# MB1075.net
KiCad netlist of a schematic drawn in Altium Designer
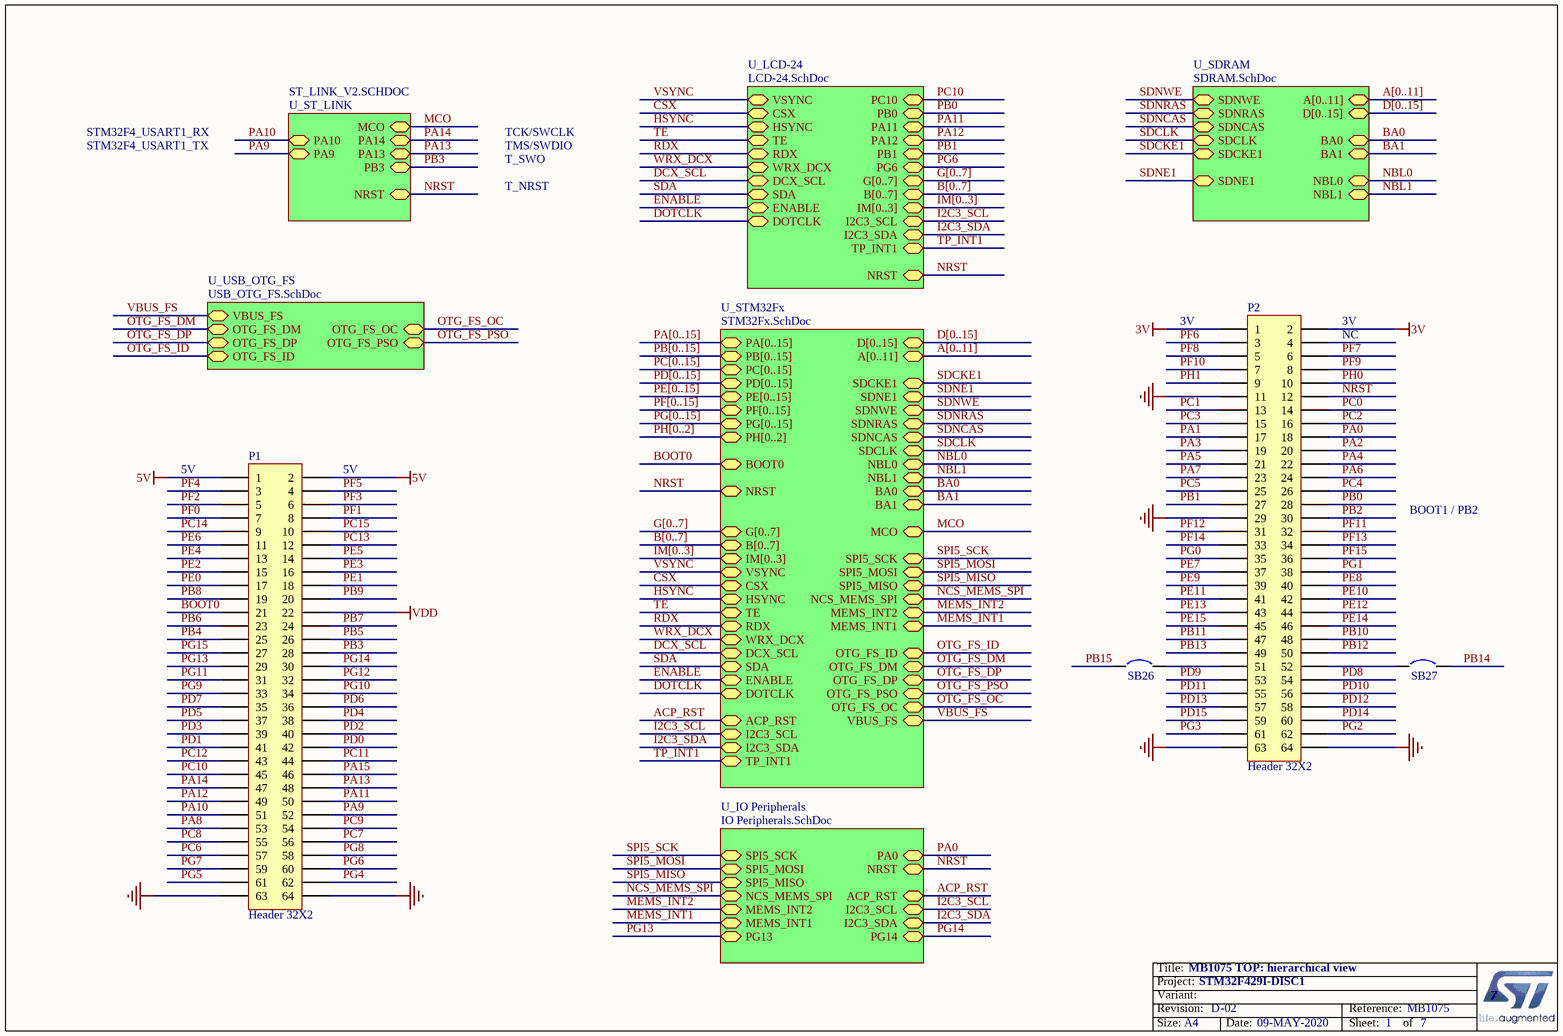
[diagram p0: MB1075.SchDoc]

(export (version "E")
  (design (tool "Eeschema 10.0.6"))
  (components
    (comp (ref "P1")
      (value "Header 32X2")
      (footprint "HDR2X32")
      (description "Header, 32-Pin, Dual row")
      (fields (field (name "PUBLISHER") "Altium Limited"))
      (libsource (lib "MCD_TOOLS") (part "Header 32X2"))
    )
    (comp (ref "P2")
      (value "Header 32X2")
      (footprint "HDR2X32")
      (description "Header, 32-Pin, Dual row")
      (fields (field (name "PUBLISHER") "Altium Limited"))
      (libsource (lib "MCD_TOOLS") (part "Header 32X2"))
    )
    (comp (ref "SB26")
      (value "Circuit Breaker")
      (footprint "JP2_SMD")
      (fields (field (name "PUBLISHER") "Altium Limited"))
      (libsource (lib "MCD_TOOLS") (part "Circuit Breaker"))
    )
    (comp (ref "SB27")
      (value "Circuit Breaker")
      (footprint "JP2_SMD")
      (fields (field (name "PUBLISHER") "Altium Limited"))
      (libsource (lib "MCD_TOOLS") (part "Circuit Breaker"))
    )
  )
  (nets
    (net (code "54") (name "/BOOT0") (class "Default")
      (node (ref "P1") (pin "21") (pinfunction "21_21") (pintype "passive"))
    )
    (net (code "72") (name "/NRST") (class "Default")
      (node (ref "P2") (pin "12") (pinfunction "12_12") (pintype "passive"))
    )
    (net (code "78") (name "/PA0") (class "Default")
      (node (ref "P2") (pin "18") (pinfunction "18_18") (pintype "passive"))
    )
    (net (code "79") (name "/PA1") (class "Default")
      (node (ref "P2") (pin "17") (pinfunction "17_17") (pintype "passive"))
    )
    (net (code "80") (name "/PA2") (class "Default")
      (node (ref "P2") (pin "20") (pinfunction "20_20") (pintype "passive"))
    )
    (net (code "81") (name "/PA3") (class "Default")
      (node (ref "P2") (pin "19") (pinfunction "19_19") (pintype "passive"))
    )
    (net (code "82") (name "/PA4") (class "Default")
      (node (ref "P2") (pin "22") (pinfunction "22_22") (pintype "passive"))
    )
    (net (code "83") (name "/PA5") (class "Default")
      (node (ref "P2") (pin "21") (pinfunction "21_21") (pintype "passive"))
    )
    (net (code "84") (name "/PA6") (class "Default")
      (node (ref "P2") (pin "24") (pinfunction "24_24") (pintype "passive"))
    )
    (net (code "85") (name "/PA7") (class "Default")
      (node (ref "P2") (pin "23") (pinfunction "23_23") (pintype "passive"))
    )
    (net (code "86") (name "/PA8") (class "Default")
      (node (ref "P1") (pin "53") (pinfunction "53_53") (pintype "passive"))
    )
    (net (code "87") (name "/PA9") (class "Default")
      (node (ref "P1") (pin "52") (pinfunction "52_52") (pintype "passive"))
    )
    (net (code "88") (name "/PA10") (class "Default")
      (node (ref "P1") (pin "51") (pinfunction "51_51") (pintype "passive"))
    )
    (net (code "89") (name "/PA11") (class "Default")
      (node (ref "P1") (pin "50") (pinfunction "50_50") (pintype "passive"))
    )
    (net (code "90") (name "/PA12") (class "Default")
      (node (ref "P1") (pin "49") (pinfunction "49_49") (pintype "passive"))
    )
    (net (code "91") (name "/PA13") (class "Default")
      (node (ref "P1") (pin "48") (pinfunction "48_48") (pintype "passive"))
    )
    (net (code "92") (name "/PA14") (class "Default")
      (node (ref "P1") (pin "47") (pinfunction "47_47") (pintype "passive"))
    )
    (net (code "93") (name "/PA15") (class "Default")
      (node (ref "P1") (pin "46") (pinfunction "46_46") (pintype "passive"))
    )
    (net (code "95") (name "/PB0") (class "Default")
      (node (ref "P2") (pin "28") (pinfunction "28_28") (pintype "passive"))
    )
    (net (code "96") (name "/PB1") (class "Default")
      (node (ref "P2") (pin "27") (pinfunction "27_27") (pintype "passive"))
    )
    (net (code "97") (name "/PB2") (class "Default")
      (node (ref "P2") (pin "30") (pinfunction "30_30") (pintype "passive"))
    )
    (net (code "98") (name "/PB3") (class "Default")
      (node (ref "P1") (pin "28") (pinfunction "28_28") (pintype "passive"))
    )
    (net (code "99") (name "/PB4") (class "Default")
      (node (ref "P1") (pin "25") (pinfunction "25_25") (pintype "passive"))
    )
    (net (code "100") (name "/PB5") (class "Default")
      (node (ref "P1") (pin "26") (pinfunction "26_26") (pintype "passive"))
    )
    (net (code "101") (name "/PB6") (class "Default")
      (node (ref "P1") (pin "23") (pinfunction "23_23") (pintype "passive"))
    )
    (net (code "102") (name "/PB7") (class "Default")
      (node (ref "P1") (pin "24") (pinfunction "24_24") (pintype "passive"))
    )
    (net (code "103") (name "/PB8") (class "Default")
      (node (ref "P1") (pin "19") (pinfunction "19_19") (pintype "passive"))
    )
    (net (code "104") (name "/PB9") (class "Default")
      (node (ref "P1") (pin "20") (pinfunction "20_20") (pintype "passive"))
    )
    (net (code "105") (name "/PB10") (class "Default")
      (node (ref "P2") (pin "48") (pinfunction "48_48") (pintype "passive"))
    )
    (net (code "106") (name "/PB11") (class "Default")
      (node (ref "P2") (pin "47") (pinfunction "47_47") (pintype "passive"))
    )
    (net (code "107") (name "/PB12") (class "Default")
      (node (ref "P2") (pin "50") (pinfunction "50_50") (pintype "passive"))
    )
    (net (code "108") (name "/PB13") (class "Default")
      (node (ref "P2") (pin "49") (pinfunction "49_49") (pintype "passive"))
    )
    (net (code "109") (name "/PB14") (class "Default")
      (node (ref "SB27") (pin "2") (pinfunction "2_2") (pintype "passive"))
    )
    (net (code "110") (name "/PB15") (class "Default")
      (node (ref "SB26") (pin "1") (pinfunction "1_1") (pintype "passive"))
    )
    (net (code "112") (name "/PC0") (class "Default")
      (node (ref "P2") (pin "14") (pinfunction "14_14") (pintype "passive"))
    )
    (net (code "113") (name "/PC1") (class "Default")
      (node (ref "P2") (pin "13") (pinfunction "13_13") (pintype "passive"))
    )
    (net (code "114") (name "/PC2") (class "Default")
      (node (ref "P2") (pin "16") (pinfunction "16_16") (pintype "passive"))
    )
    (net (code "115") (name "/PC3") (class "Default")
      (node (ref "P2") (pin "15") (pinfunction "15_15") (pintype "passive"))
    )
    (net (code "116") (name "/PC4") (class "Default")
      (node (ref "P2") (pin "26") (pinfunction "26_26") (pintype "passive"))
    )
    (net (code "117") (name "/PC5") (class "Default")
      (node (ref "P2") (pin "25") (pinfunction "25_25") (pintype "passive"))
    )
    (net (code "118") (name "/PC6") (class "Default")
      (node (ref "P1") (pin "57") (pinfunction "57_57") (pintype "passive"))
    )
    (net (code "119") (name "/PC7") (class "Default")
      (node (ref "P1") (pin "56") (pinfunction "56_56") (pintype "passive"))
    )
    (net (code "120") (name "/PC8") (class "Default")
      (node (ref "P1") (pin "55") (pinfunction "55_55") (pintype "passive"))
    )
    (net (code "121") (name "/PC9") (class "Default")
      (node (ref "P1") (pin "54") (pinfunction "54_54") (pintype "passive"))
    )
    (net (code "122") (name "/PC10") (class "Default")
      (node (ref "P1") (pin "45") (pinfunction "45_45") (pintype "passive"))
    )
    (net (code "123") (name "/PC11") (class "Default")
      (node (ref "P1") (pin "44") (pinfunction "44_44") (pintype "passive"))
    )
    (net (code "124") (name "/PC12") (class "Default")
      (node (ref "P1") (pin "43") (pinfunction "43_43") (pintype "passive"))
    )
    (net (code "125") (name "/PC13") (class "Default")
      (node (ref "P1") (pin "12") (pinfunction "12_12") (pintype "passive"))
    )
    (net (code "126") (name "/PC14") (class "Default")
      (node (ref "P1") (pin "9") (pinfunction "9_9") (pintype "passive"))
    )
    (net (code "127") (name "/PC15") (class "Default")
      (node (ref "P1") (pin "10") (pinfunction "10_10") (pintype "passive"))
    )
    (net (code "129") (name "/PD0") (class "Default")
      (node (ref "P1") (pin "42") (pinfunction "42_42") (pintype "passive"))
    )
    (net (code "130") (name "/PD1") (class "Default")
      (node (ref "P1") (pin "41") (pinfunction "41_41") (pintype "passive"))
    )
    (net (code "131") (name "/PD2") (class "Default")
      (node (ref "P1") (pin "40") (pinfunction "40_40") (pintype "passive"))
    )
    (net (code "132") (name "/PD3") (class "Default")
      (node (ref "P1") (pin "39") (pinfunction "39_39") (pintype "passive"))
    )
    (net (code "133") (name "/PD4") (class "Default")
      (node (ref "P1") (pin "38") (pinfunction "38_38") (pintype "passive"))
    )
    (net (code "134") (name "/PD5") (class "Default")
      (node (ref "P1") (pin "37") (pinfunction "37_37") (pintype "passive"))
    )
    (net (code "135") (name "/PD6") (class "Default")
      (node (ref "P1") (pin "36") (pinfunction "36_36") (pintype "passive"))
    )
    (net (code "136") (name "/PD7") (class "Default")
      (node (ref "P1") (pin "35") (pinfunction "35_35") (pintype "passive"))
    )
    (net (code "137") (name "/PD8") (class "Default")
      (node (ref "P2") (pin "54") (pinfunction "54_54") (pintype "passive"))
    )
    (net (code "138") (name "/PD9") (class "Default")
      (node (ref "P2") (pin "53") (pinfunction "53_53") (pintype "passive"))
    )
    (net (code "139") (name "/PD10") (class "Default")
      (node (ref "P2") (pin "56") (pinfunction "56_56") (pintype "passive"))
    )
    (net (code "140") (name "/PD11") (class "Default")
      (node (ref "P2") (pin "55") (pinfunction "55_55") (pintype "passive"))
    )
    (net (code "141") (name "/PD12") (class "Default")
      (node (ref "P2") (pin "58") (pinfunction "58_58") (pintype "passive"))
    )
    (net (code "142") (name "/PD13") (class "Default")
      (node (ref "P2") (pin "57") (pinfunction "57_57") (pintype "passive"))
    )
    (net (code "143") (name "/PD14") (class "Default")
      (node (ref "P2") (pin "60") (pinfunction "60_60") (pintype "passive"))
    )
    (net (code "144") (name "/PD15") (class "Default")
      (node (ref "P2") (pin "59") (pinfunction "59_59") (pintype "passive"))
    )
    (net (code "146") (name "/PE0") (class "Default")
      (node (ref "P1") (pin "17") (pinfunction "17_17") (pintype "passive"))
    )
    (net (code "147") (name "/PE1") (class "Default")
      (node (ref "P1") (pin "18") (pinfunction "18_18") (pintype "passive"))
    )
    (net (code "148") (name "/PE2") (class "Default")
      (node (ref "P1") (pin "15") (pinfunction "15_15") (pintype "passive"))
    )
    (net (code "149") (name "/PE3") (class "Default")
      (node (ref "P1") (pin "16") (pinfunction "16_16") (pintype "passive"))
    )
    (net (code "150") (name "/PE4") (class "Default")
      (node (ref "P1") (pin "13") (pinfunction "13_13") (pintype "passive"))
    )
    (net (code "151") (name "/PE5") (class "Default")
      (node (ref "P1") (pin "14") (pinfunction "14_14") (pintype "passive"))
    )
    (net (code "152") (name "/PE6") (class "Default")
      (node (ref "P1") (pin "11") (pinfunction "11_11") (pintype "passive"))
    )
    (net (code "153") (name "/PE7") (class "Default")
      (node (ref "P2") (pin "37") (pinfunction "37_37") (pintype "passive"))
    )
    (net (code "154") (name "/PE8") (class "Default")
      (node (ref "P2") (pin "40") (pinfunction "40_40") (pintype "passive"))
    )
    (net (code "155") (name "/PE9") (class "Default")
      (node (ref "P2") (pin "39") (pinfunction "39_39") (pintype "passive"))
    )
    (net (code "156") (name "/PE10") (class "Default")
      (node (ref "P2") (pin "42") (pinfunction "42_42") (pintype "passive"))
    )
    (net (code "157") (name "/PE11") (class "Default")
      (node (ref "P2") (pin "41") (pinfunction "41_41") (pintype "passive"))
    )
    (net (code "158") (name "/PE12") (class "Default")
      (node (ref "P2") (pin "44") (pinfunction "44_44") (pintype "passive"))
    )
    (net (code "159") (name "/PE13") (class "Default")
      (node (ref "P2") (pin "43") (pinfunction "43_43") (pintype "passive"))
    )
    (net (code "160") (name "/PE14") (class "Default")
      (node (ref "P2") (pin "46") (pinfunction "46_46") (pintype "passive"))
    )
    (net (code "161") (name "/PE15") (class "Default")
      (node (ref "P2") (pin "45") (pinfunction "45_45") (pintype "passive"))
    )
    (net (code "163") (name "/PF0") (class "Default")
      (node (ref "P1") (pin "7") (pinfunction "7_7") (pintype "passive"))
    )
    (net (code "164") (name "/PF1") (class "Default")
      (node (ref "P1") (pin "8") (pinfunction "8_8") (pintype "passive"))
    )
    (net (code "165") (name "/PF2") (class "Default")
      (node (ref "P1") (pin "5") (pinfunction "5_5") (pintype "passive"))
    )
    (net (code "166") (name "/PF3") (class "Default")
      (node (ref "P1") (pin "6") (pinfunction "6_6") (pintype "passive"))
    )
    (net (code "167") (name "/PF4") (class "Default")
      (node (ref "P1") (pin "3") (pinfunction "3_3") (pintype "passive"))
    )
    (net (code "168") (name "/PF5") (class "Default")
      (node (ref "P1") (pin "4") (pinfunction "4_4") (pintype "passive"))
    )
    (net (code "169") (name "/PF6") (class "Default")
      (node (ref "P2") (pin "3") (pinfunction "3_3") (pintype "passive"))
    )
    (net (code "170") (name "/PF7") (class "Default")
      (node (ref "P2") (pin "6") (pinfunction "6_6") (pintype "passive"))
    )
    (net (code "171") (name "/PF8") (class "Default")
      (node (ref "P2") (pin "5") (pinfunction "5_5") (pintype "passive"))
    )
    (net (code "172") (name "/PF9") (class "Default")
      (node (ref "P2") (pin "8") (pinfunction "8_8") (pintype "passive"))
    )
    (net (code "173") (name "/PF10") (class "Default")
      (node (ref "P2") (pin "7") (pinfunction "7_7") (pintype "passive"))
    )
    (net (code "174") (name "/PF11") (class "Default")
      (node (ref "P2") (pin "32") (pinfunction "32_32") (pintype "passive"))
    )
    (net (code "175") (name "/PF12") (class "Default")
      (node (ref "P2") (pin "31") (pinfunction "31_31") (pintype "passive"))
    )
    (net (code "176") (name "/PF13") (class "Default")
      (node (ref "P2") (pin "34") (pinfunction "34_34") (pintype "passive"))
    )
    (net (code "177") (name "/PF14") (class "Default")
      (node (ref "P2") (pin "33") (pinfunction "33_33") (pintype "passive"))
    )
    (net (code "178") (name "/PF15") (class "Default")
      (node (ref "P2") (pin "36") (pinfunction "36_36") (pintype "passive"))
    )
    (net (code "180") (name "/PG0") (class "Default")
      (node (ref "P2") (pin "35") (pinfunction "35_35") (pintype "passive"))
    )
    (net (code "181") (name "/PG1") (class "Default")
      (node (ref "P2") (pin "38") (pinfunction "38_38") (pintype "passive"))
    )
    (net (code "182") (name "/PG2") (class "Default")
      (node (ref "P2") (pin "62") (pinfunction "62_62") (pintype "passive"))
    )
    (net (code "183") (name "/PG3") (class "Default")
      (node (ref "P2") (pin "61") (pinfunction "61_61") (pintype "passive"))
    )
    (net (code "184") (name "/PG4") (class "Default")
      (node (ref "P1") (pin "62") (pinfunction "62_62") (pintype "passive"))
    )
    (net (code "185") (name "/PG5") (class "Default")
      (node (ref "P1") (pin "61") (pinfunction "61_61") (pintype "passive"))
    )
    (net (code "186") (name "/PG6") (class "Default")
      (node (ref "P1") (pin "60") (pinfunction "60_60") (pintype "passive"))
    )
    (net (code "187") (name "/PG7") (class "Default")
      (node (ref "P1") (pin "59") (pinfunction "59_59") (pintype "passive"))
    )
    (net (code "188") (name "/PG8") (class "Default")
      (node (ref "P1") (pin "58") (pinfunction "58_58") (pintype "passive"))
    )
    (net (code "189") (name "/PG9") (class "Default")
      (node (ref "P1") (pin "33") (pinfunction "33_33") (pintype "passive"))
    )
    (net (code "190") (name "/PG10") (class "Default")
      (node (ref "P1") (pin "34") (pinfunction "34_34") (pintype "passive"))
    )
    (net (code "191") (name "/PG11") (class "Default")
      (node (ref "P1") (pin "31") (pinfunction "31_31") (pintype "passive"))
    )
    (net (code "192") (name "/PG12") (class "Default")
      (node (ref "P1") (pin "32") (pinfunction "32_32") (pintype "passive"))
    )
    (net (code "193") (name "/PG13") (class "Default")
      (node (ref "P1") (pin "29") (pinfunction "29_29") (pintype "passive"))
    )
    (net (code "194") (name "/PG14") (class "Default")
      (node (ref "P1") (pin "30") (pinfunction "30_30") (pintype "passive"))
    )
    (net (code "195") (name "/PG15") (class "Default")
      (node (ref "P1") (pin "27") (pinfunction "27_27") (pintype "passive"))
    )
    (net (code "197") (name "/PH0") (class "Default")
      (node (ref "P2") (pin "10") (pinfunction "10_10") (pintype "passive"))
    )
    (net (code "198") (name "/PH1") (class "Default")
      (node (ref "P2") (pin "9") (pinfunction "9_9") (pintype "passive"))
    )
    (net (code "216") (name "3V") (class "Default")
      (node (ref "P2") (pin "1") (pinfunction "1_1") (pintype "passive"))
      (node (ref "P2") (pin "2") (pinfunction "2_2") (pintype "passive"))
    )
    (net (code "217") (name "5V") (class "Default")
      (node (ref "P1") (pin "1") (pinfunction "1_1") (pintype "passive"))
      (node (ref "P1") (pin "2") (pinfunction "2_2") (pintype "passive"))
    )
    (net (code "218") (name "GND") (class "Default")
      (node (ref "P1") (pin "63") (pinfunction "63_63") (pintype "passive"))
      (node (ref "P1") (pin "64") (pinfunction "64_64") (pintype "passive"))
      (node (ref "P2") (pin "11") (pinfunction "11_11") (pintype "passive"))
      (node (ref "P2") (pin "29") (pinfunction "29_29") (pintype "passive"))
      (node (ref "P2") (pin "63") (pinfunction "63_63") (pintype "passive"))
      (node (ref "P2") (pin "64") (pinfunction "64_64") (pintype "passive"))
    )
    (net (code "219") (name "Net-(P2-Pad51)") (class "Default")
      (node (ref "P2") (pin "51") (pinfunction "51_51") (pintype "passive"))
      (node (ref "SB26") (pin "2") (pinfunction "2_2") (pintype "passive"))
    )
    (net (code "220") (name "Net-(P2-Pad52)") (class "Default")
      (node (ref "P2") (pin "52") (pinfunction "52_52") (pintype "passive"))
      (node (ref "SB27") (pin "1") (pinfunction "1_1") (pintype "passive"))
    )
    (net (code "221") (name "VDD") (class "Default")
      (node (ref "P1") (pin "22") (pinfunction "22_22") (pintype "passive"))
    )
    (net (code "222") (name "unconnected-(P2-Pad4)") (class "Default")
      (node (ref "P2") (pin "4") (pinfunction "4_4") (pintype "passive"))
    )
  )
)
